# nucleo.net
KiCad netlist of a schematic drawn in EAGLE
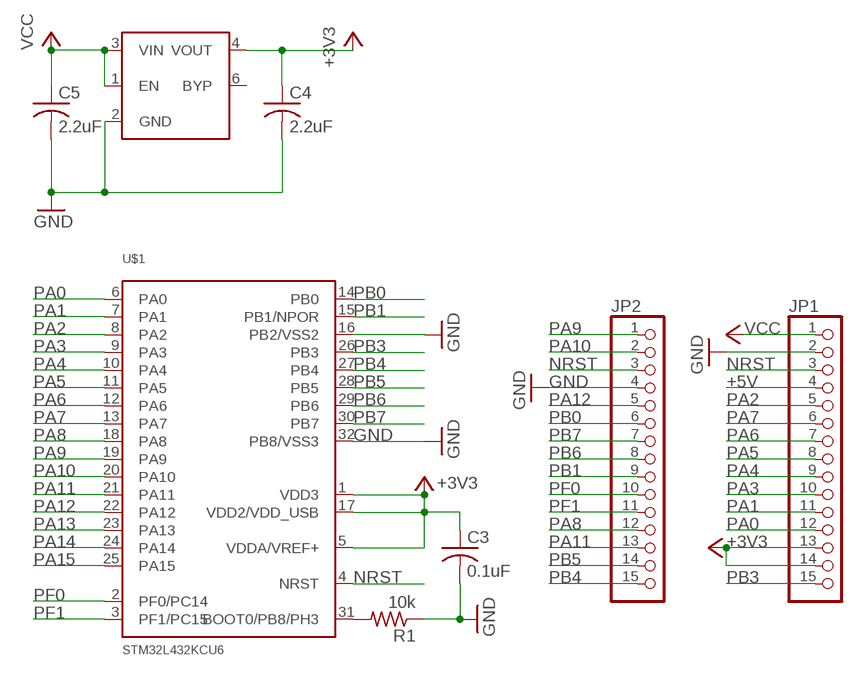
[diagram p0: schematic, sheet 1]

(export (version "E")
  (design (tool "Eeschema 10.0.6"))
  (components
    (comp (ref "C3")
      (value "0.1uF")
      (footprint "eagle-import:C0402")
      (libsource (lib "eagle-import") (part "C-USC0402"))
    )
    (comp (ref "C4")
      (value "2.2uF")
      (footprint "eagle-import:C0402")
      (libsource (lib "eagle-import") (part "C-USC0402"))
    )
    (comp (ref "C5")
      (value "2.2uF")
      (footprint "eagle-import:C0402")
      (libsource (lib "eagle-import") (part "C-USC0402"))
    )
    (comp (ref "JP1")
      (value "PINHD-1X15")
      (footprint "eagle-import:1X15")
      (libsource (lib "eagle-import") (part "PINHD-1X15"))
    )
    (comp (ref "JP2")
      (value "PINHD-1X15")
      (footprint "eagle-import:1X15")
      (libsource (lib "eagle-import") (part "PINHD-1X15"))
    )
    (comp (ref "R1")
      (value "10k")
      (footprint "eagle-import:R0402")
      (libsource (lib "eagle-import") (part "R-US_R0402"))
    )
    (comp (ref "U$1")
      (value "STM32L432KCU6")
      (footprint "eagle-import:QFN-32")
      (libsource (lib "eagle-import") (part "STM32L432KCU6"))
    )
    (comp (ref "U$3")
      (value "MIC5305-MLF")
      (footprint "eagle-import:MLF-6")
      (libsource (lib "eagle-import") (part "MIC5305-MLF"))
    )
  )
  (nets
    (net (code "1") (name "+3V3") (class "Default")
      (node (ref "C3") (pin "1") (pinfunction "1_1") (pintype "passive"))
      (node (ref "C4") (pin "1") (pinfunction "1_1") (pintype "passive"))
      (node (ref "JP1") (pin "13") (pinfunction "13_13") (pintype "passive"))
      (node (ref "JP1") (pin "14") (pinfunction "14_14") (pintype "passive"))
      (node (ref "U$1") (pin "1") (pinfunction "VDD3_1") (pintype "bidirectional"))
      (node (ref "U$1") (pin "17") (pinfunction "VDD2/VDD_USB_17") (pintype "bidirectional"))
      (node (ref "U$1") (pin "5") (pinfunction "VDDA/VREF+_5") (pintype "bidirectional"))
      (node (ref "U$3") (pin "4") (pinfunction "VOUT_4") (pintype "bidirectional"))
    )
    (net (code "2") (name "/+5V") (class "Default")
      (node (ref "JP1") (pin "4") (pinfunction "4_4") (pintype "passive"))
    )
    (net (code "3") (name "/NRST") (class "Default")
      (node (ref "JP1") (pin "3") (pinfunction "3_3") (pintype "passive"))
      (node (ref "JP2") (pin "3") (pinfunction "3_3") (pintype "passive"))
      (node (ref "U$1") (pin "4") (pinfunction "NRST_4") (pintype "bidirectional"))
    )
    (net (code "4") (name "/PA0") (class "Default")
      (node (ref "JP1") (pin "12") (pinfunction "12_12") (pintype "passive"))
      (node (ref "U$1") (pin "6") (pinfunction "PA0_6") (pintype "bidirectional"))
    )
    (net (code "5") (name "/PA1") (class "Default")
      (node (ref "JP1") (pin "11") (pinfunction "11_11") (pintype "passive"))
      (node (ref "U$1") (pin "7") (pinfunction "PA1_7") (pintype "bidirectional"))
    )
    (net (code "6") (name "/PA2") (class "Default")
      (node (ref "JP1") (pin "5") (pinfunction "5_5") (pintype "passive"))
      (node (ref "U$1") (pin "8") (pinfunction "PA2_8") (pintype "bidirectional"))
    )
    (net (code "7") (name "/PA3") (class "Default")
      (node (ref "JP1") (pin "10") (pinfunction "10_10") (pintype "passive"))
      (node (ref "U$1") (pin "9") (pinfunction "PA3_9") (pintype "bidirectional"))
    )
    (net (code "8") (name "/PA4") (class "Default")
      (node (ref "JP1") (pin "9") (pinfunction "9_9") (pintype "passive"))
      (node (ref "U$1") (pin "10") (pinfunction "PA4_10") (pintype "bidirectional"))
    )
    (net (code "9") (name "/PA5") (class "Default")
      (node (ref "JP1") (pin "8") (pinfunction "8_8") (pintype "passive"))
      (node (ref "U$1") (pin "11") (pinfunction "PA5_11") (pintype "bidirectional"))
    )
    (net (code "10") (name "/PA6") (class "Default")
      (node (ref "JP1") (pin "7") (pinfunction "7_7") (pintype "passive"))
      (node (ref "U$1") (pin "12") (pinfunction "PA6_12") (pintype "bidirectional"))
    )
    (net (code "11") (name "/PA7") (class "Default")
      (node (ref "JP1") (pin "6") (pinfunction "6_6") (pintype "passive"))
      (node (ref "U$1") (pin "13") (pinfunction "PA7_13") (pintype "bidirectional"))
    )
    (net (code "12") (name "/PA8") (class "Default")
      (node (ref "JP2") (pin "12") (pinfunction "12_12") (pintype "passive"))
      (node (ref "U$1") (pin "18") (pinfunction "PA8_18") (pintype "bidirectional"))
    )
    (net (code "13") (name "/PA9") (class "Default")
      (node (ref "JP2") (pin "1") (pinfunction "1_1") (pintype "passive"))
      (node (ref "U$1") (pin "19") (pinfunction "PA9_19") (pintype "bidirectional"))
    )
    (net (code "14") (name "/PA10") (class "Default")
      (node (ref "JP2") (pin "2") (pinfunction "2_2") (pintype "passive"))
      (node (ref "U$1") (pin "20") (pinfunction "PA10_20") (pintype "bidirectional"))
    )
    (net (code "15") (name "/PA11") (class "Default")
      (node (ref "JP2") (pin "13") (pinfunction "13_13") (pintype "passive"))
      (node (ref "U$1") (pin "21") (pinfunction "PA11_21") (pintype "bidirectional"))
    )
    (net (code "16") (name "/PA12") (class "Default")
      (node (ref "JP2") (pin "5") (pinfunction "5_5") (pintype "passive"))
      (node (ref "U$1") (pin "22") (pinfunction "PA12_22") (pintype "bidirectional"))
    )
    (net (code "17") (name "/PA13") (class "Default")
      (node (ref "U$1") (pin "23") (pinfunction "PA13_23") (pintype "bidirectional"))
    )
    (net (code "18") (name "/PA14") (class "Default")
      (node (ref "U$1") (pin "24") (pinfunction "PA14_24") (pintype "bidirectional"))
    )
    (net (code "19") (name "/PA15") (class "Default")
      (node (ref "U$1") (pin "25") (pinfunction "PA15_25") (pintype "bidirectional"))
    )
    (net (code "20") (name "/PB0") (class "Default")
      (node (ref "JP2") (pin "6") (pinfunction "6_6") (pintype "passive"))
      (node (ref "U$1") (pin "14") (pinfunction "PB0_14") (pintype "bidirectional"))
    )
    (net (code "21") (name "/PB1") (class "Default")
      (node (ref "JP2") (pin "9") (pinfunction "9_9") (pintype "passive"))
      (node (ref "U$1") (pin "15") (pinfunction "PB1/NPOR_15") (pintype "bidirectional"))
    )
    (net (code "22") (name "/PB3") (class "Default")
      (node (ref "JP1") (pin "15") (pinfunction "15_15") (pintype "passive"))
      (node (ref "U$1") (pin "26") (pinfunction "PB3_26") (pintype "bidirectional"))
    )
    (net (code "23") (name "/PB4") (class "Default")
      (node (ref "JP2") (pin "15") (pinfunction "15_15") (pintype "passive"))
      (node (ref "U$1") (pin "27") (pinfunction "PB4_27") (pintype "bidirectional"))
    )
    (net (code "24") (name "/PB5") (class "Default")
      (node (ref "JP2") (pin "14") (pinfunction "14_14") (pintype "passive"))
      (node (ref "U$1") (pin "28") (pinfunction "PB5_28") (pintype "bidirectional"))
    )
    (net (code "25") (name "/PB6") (class "Default")
      (node (ref "JP2") (pin "8") (pinfunction "8_8") (pintype "passive"))
      (node (ref "U$1") (pin "29") (pinfunction "PB6_29") (pintype "bidirectional"))
    )
    (net (code "26") (name "/PB7") (class "Default")
      (node (ref "JP2") (pin "7") (pinfunction "7_7") (pintype "passive"))
      (node (ref "U$1") (pin "30") (pinfunction "PB7_30") (pintype "bidirectional"))
    )
    (net (code "27") (name "/PF0") (class "Default")
      (node (ref "JP2") (pin "10") (pinfunction "10_10") (pintype "passive"))
      (node (ref "U$1") (pin "2") (pinfunction "PF0/PC14_2") (pintype "bidirectional"))
    )
    (net (code "28") (name "/PF1") (class "Default")
      (node (ref "JP2") (pin "11") (pinfunction "11_11") (pintype "passive"))
      (node (ref "U$1") (pin "3") (pinfunction "PF1/PC15_3") (pintype "bidirectional"))
    )
    (net (code "29") (name "GND") (class "Default")
      (node (ref "C3") (pin "2") (pinfunction "2_2") (pintype "passive"))
      (node (ref "C4") (pin "2") (pinfunction "2_2") (pintype "passive"))
      (node (ref "C5") (pin "2") (pinfunction "2_2") (pintype "passive"))
      (node (ref "JP1") (pin "2") (pinfunction "2_2") (pintype "passive"))
      (node (ref "JP2") (pin "4") (pinfunction "4_4") (pintype "passive"))
      (node (ref "R1") (pin "1") (pinfunction "1_1") (pintype "passive"))
      (node (ref "U$1") (pin "16") (pinfunction "PB2/VSS2_16") (pintype "bidirectional"))
      (node (ref "U$1") (pin "32") (pinfunction "PB8/VSS3_32") (pintype "bidirectional"))
      (node (ref "U$3") (pin "2") (pinfunction "GND_2") (pintype "bidirectional"))
    )
    (net (code "30") (name "Net-(U$1-BOOT0{slash}PB8{slash}PH3)") (class "Default")
      (node (ref "R1") (pin "2") (pinfunction "2_2") (pintype "passive"))
      (node (ref "U$1") (pin "31") (pinfunction "BOOT0/PB8/PH3_31") (pintype "bidirectional"))
    )
    (net (code "31") (name "VCC") (class "Default")
      (node (ref "C5") (pin "1") (pinfunction "1_1") (pintype "passive"))
      (node (ref "JP1") (pin "1") (pinfunction "1_1") (pintype "passive"))
      (node (ref "U$3") (pin "1") (pinfunction "EN_1") (pintype "bidirectional"))
      (node (ref "U$3") (pin "3") (pinfunction "VIN_3") (pintype "bidirectional"))
    )
    (net (code "32") (name "unconnected-(U$3-BYP-Pad6)") (class "Default")
      (node (ref "U$3") (pin "6") (pinfunction "BYP_6") (pintype "bidirectional"))
    )
  )
)
